# Sheet1.net
KiCad netlist of a schematic drawn in Altium Designer
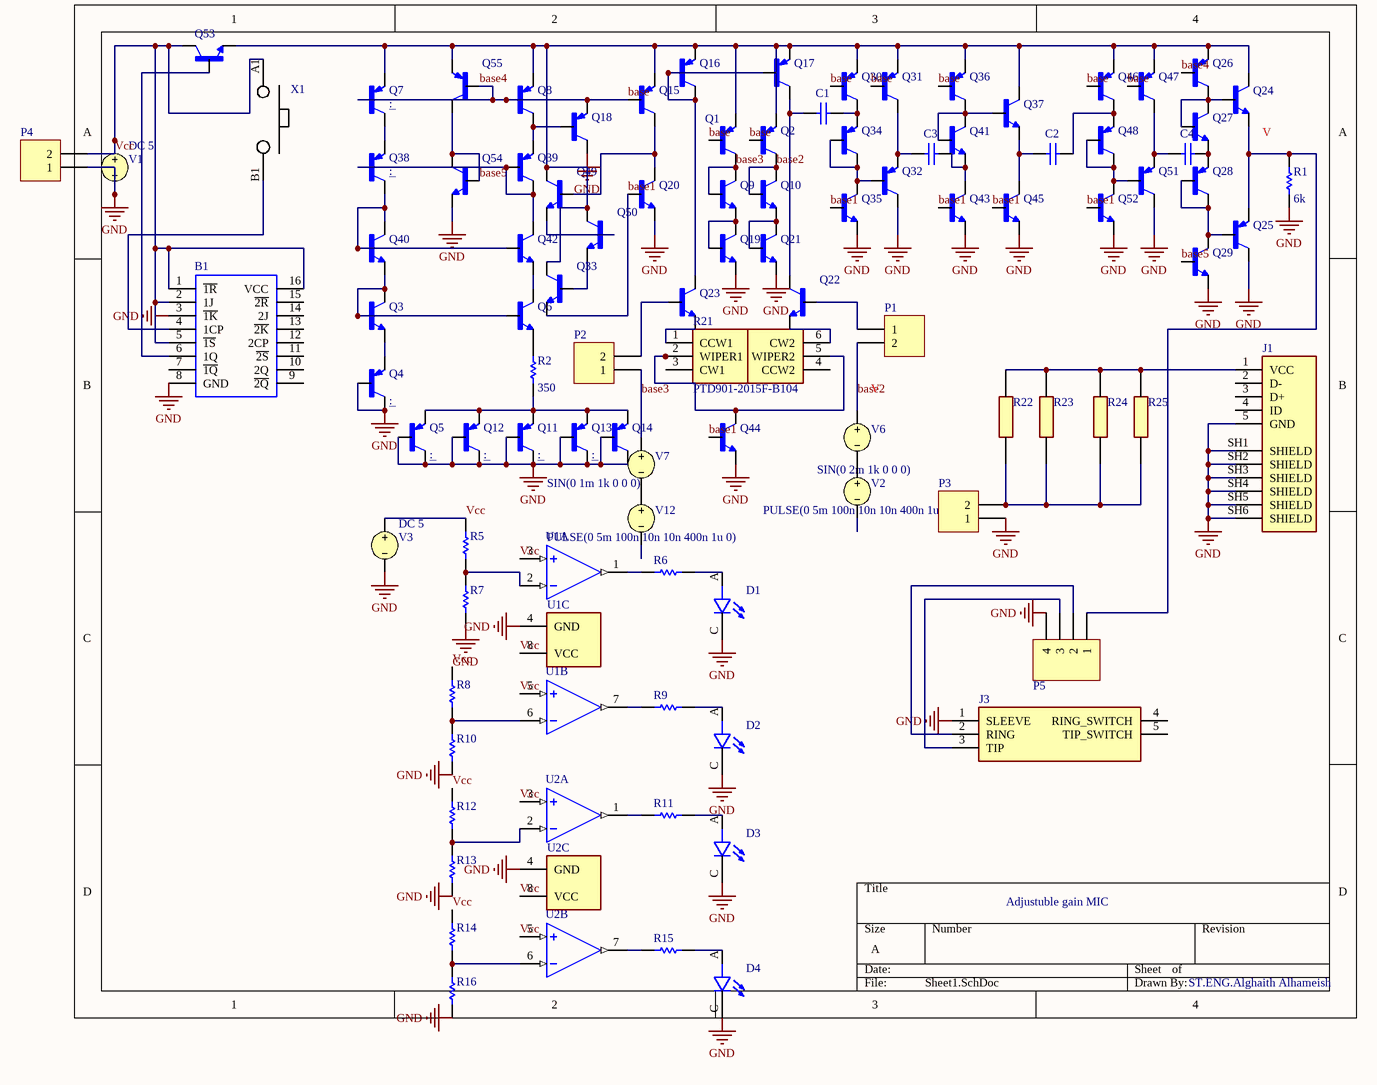
[diagram p0: Sheet1.SchDoc]

(export (version "E")
  (design (tool "Eeschema 10.0.6"))
  (components
    (comp (ref "B1")
      (value "CD74HC109E")
      (footprint "DIP794W53P254L1930H508Q16N")
      (description "High Speed CMOS Logic Dual Positive-Edge-Triggered J-K Flip-Flops with Set and Reset")
      (fields (field (name "MOUSER PART NUMBER") "595-CD74HC109E"))
      (libsource (lib "CD74HC109E") (part "CD74HC109E"))
    )
    (comp (ref "C1")
      (value "Cap")
      (footprint "PCBComponent_1")
      (description "Capacitor")
      (fields (field (name "PUBLISHER") "Altium Limited"))
      (libsource (lib "Miscellaneous Devices") (part "Cap"))
    )
    (comp (ref "C2")
      (value "Cap")
      (footprint "PCBComponent_1")
      (description "Capacitor")
      (fields (field (name "PUBLISHER") "Altium Limited"))
      (libsource (lib "Miscellaneous Devices") (part "Cap"))
    )
    (comp (ref "C3")
      (value "Cap")
      (footprint "PCBComponent_1")
      (description "Capacitor")
      (fields (field (name "PUBLISHER") "Altium Limited"))
      (libsource (lib "Miscellaneous Devices") (part "Cap"))
    )
    (comp (ref "C4")
      (value "Cap")
      (footprint "PCBComponent_1")
      (description "Capacitor")
      (fields (field (name "PUBLISHER") "Altium Limited"))
      (libsource (lib "Miscellaneous Devices") (part "Cap"))
    )
    (comp (ref "D1")
      (value "151054RS03000")
      (footprint "LED_151054RS03000")
      (description "Red 623nm LED Indication - Discrete 1.9V Radial")
      (libsource (lib "151054RS03000") (part "151054RS03000"))
    )
    (comp (ref "D2")
      (value "151054RS03000")
      (footprint "LED_151054RS03000")
      (description "Red 623nm LED Indication - Discrete 1.9V Radial")
      (libsource (lib "151054RS03000") (part "151054RS03000"))
    )
    (comp (ref "D3")
      (value "151054RS03000")
      (footprint "LED_151054RS03000")
      (description "Red 623nm LED Indication - Discrete 1.9V Radial")
      (libsource (lib "151054RS03000") (part "151054RS03000"))
    )
    (comp (ref "D4")
      (value "151054RS03000")
      (footprint "LED_151054RS03000")
      (description "Red 623nm LED Indication - Discrete 1.9V Radial")
      (libsource (lib "151054RS03000") (part "151054RS03000"))
    )
    (comp (ref "J1")
      (value "1932788-1")
      (footprint "TE_1932788-1")
      (description "USB - micro B USB 2.0 Receptacle Connector 5 Position Surface Mount, Right Angle")
      (fields (field (name "MF") "TE Connectivity"))
      (libsource (lib "1932788-1") (part "1932788-1"))
    )
    (comp (ref "J3")
      (value "35RASMT4BHNTRX")
      (footprint "35RASMT4BHNTRX")
      (description "Phone Connectors SMT 3.5MM PHONE JACK")
      (fields (field (name "MOUSER PART NUMBER") "502-35RASMT4BHNTRX"))
      (libsource (lib "35RASMT4BHNTRX") (part "35RASMT4BHNTRX"))
    )
    (comp (ref "P1")
      (value "Header 2")
      (footprint "HDR1X2")
      (description "Header, 2-Pin")
      (fields (field (name "PUBLISHER") "Altium Limited"))
      (libsource (lib "") (part "Header 2_1"))
    )
    (comp (ref "P2")
      (value "Header 2")
      (footprint "HDR1X2")
      (description "Header, 2-Pin")
      (fields (field (name "PUBLISHER") "Altium Limited"))
      (libsource (lib "Miscellaneous Connectors") (part "Header 2"))
    )
    (comp (ref "P3")
      (value "Header 2")
      (footprint "HDR1X2")
      (description "Header, 2-Pin")
      (fields (field (name "PUBLISHER") "Altium Limited"))
      (libsource (lib "Miscellaneous Connectors") (part "Header 2"))
    )
    (comp (ref "P4")
      (value "Header 2")
      (footprint "HDR1X2")
      (description "Header, 2-Pin")
      (fields (field (name "PUBLISHER") "Altium Limited"))
      (libsource (lib "Miscellaneous Connectors") (part "Header 2"))
    )
    (comp (ref "P5")
      (value "Header 4")
      (footprint "HDR1X4")
      (description "Header, 4-Pin")
      (fields (field (name "PUBLISHER") "Altium Limited"))
      (libsource (lib "Miscellaneous Connectors") (part "Header 4"))
    )
    (comp (ref "Q1")
      (value "BC557BRL1G")
      (footprint "TO127P254X732-3")
      (description "Bipolar (BJT) Transistor PNP 45V 100mA 320MHz 625mW Through Hole TO-92-3")
      (fields (field (name "MF") "ON Semiconductor"))
      (libsource (lib "BC557BRL1G") (part "BC557BRL1G"))
    )
    (comp (ref "Q2")
      (value "BC557BRL1G")
      (footprint "TO127P254X732-3")
      (description "Bipolar (BJT) Transistor PNP 45V 100mA 320MHz 625mW Through Hole TO-92-3")
      (fields (field (name "MF") "ON Semiconductor"))
      (libsource (lib "BC557BRL1G") (part "BC557BRL1G"))
    )
    (comp (ref "Q3")
      (value "BC337-40_A1G")
      (footprint "TO127P254X732-3")
      (description "TO-92, 50V, 0.8A, NPN Bipolar Transistor")
      (fields (field (name "MP") "BC337-40 A1G") (field (name "MF") "Taiwan Semiconductor"))
      (libsource (lib "BC337-40_A1G") (part "BC337-40_A1G"))
    )
    (comp (ref "Q4")
      (value "BC557BRL1G")
      (footprint "TO127P254X732-3")
      (description "Bipolar (BJT) Transistor PNP 45V 100mA 320MHz 625mW Through Hole TO-92-3")
      (fields (field (name "MF") "ON Semiconductor"))
      (libsource (lib "BC557BRL1G") (part "BC557BRL1G"))
    )
    (comp (ref "Q5")
      (value "BC557BRL1G")
      (footprint "TO127P254X732-3")
      (description "Bipolar (BJT) Transistor PNP 45V 100mA 320MHz 625mW Through Hole TO-92-3")
      (fields (field (name "MF") "ON Semiconductor"))
      (libsource (lib "BC557BRL1G") (part "BC557BRL1G"))
    )
    (comp (ref "Q6")
      (value "BC337-40_A1G")
      (footprint "TO127P254X732-3")
      (description "TO-92, 50V, 0.8A, NPN Bipolar Transistor")
      (fields (field (name "MP") "BC337-40 A1G") (field (name "MF") "Taiwan Semiconductor"))
      (libsource (lib "BC337-40_A1G") (part "BC337-40_A1G"))
    )
    (comp (ref "Q7")
      (value "BC557BRL1G")
      (footprint "TO127P254X732-3")
      (description "Bipolar (BJT) Transistor PNP 45V 100mA 320MHz 625mW Through Hole TO-92-3 Manufacturer")
      (fields (field (name "MF") "ON Semiconductor"))
      (libsource (lib "BC557BRL1G") (part "BC557BRL1G"))
    )
    (comp (ref "Q8")
      (value "BC557BRL1G")
      (footprint "TO127P254X732-3")
      (description "Bipolar (BJT) Transistor PNP 45V 100mA 320MHz 625mW Through Hole TO-92-3")
      (fields (field (name "MF") "ON Semiconductor"))
      (libsource (lib "BC557BRL1G") (part "BC557BRL1G"))
    )
    (comp (ref "Q9")
      (value "BC337-40_A1G")
      (footprint "TO127P254X732-3")
      (description "TO-92, 50V, 0.8A, NPN Bipolar Transistor")
      (fields (field (name "MP") "BC337-40 A1G") (field (name "MF") "Taiwan Semiconductor"))
      (libsource (lib "BC337-40_A1G") (part "BC337-40_A1G"))
    )
    (comp (ref "Q10")
      (value "BC337-40_A1G")
      (footprint "TO127P254X732-3")
      (description "TO-92, 50V, 0.8A, NPN Bipolar Transistor")
      (fields (field (name "MP") "BC337-40 A1G") (field (name "MF") "Taiwan Semiconductor"))
      (libsource (lib "BC337-40_A1G") (part "BC337-40_A1G"))
    )
    (comp (ref "Q11")
      (value "BC557BRL1G")
      (footprint "TO127P254X732-3")
      (description "Bipolar (BJT) Transistor PNP 45V 100mA 320MHz 625mW Through Hole TO-92-3")
      (fields (field (name "MF") "ON Semiconductor"))
      (libsource (lib "BC557BRL1G") (part "BC557BRL1G"))
    )
    (comp (ref "Q12")
      (value "BC557BRL1G")
      (footprint "TO127P254X732-3")
      (description "Bipolar (BJT) Transistor PNP 45V 100mA 320MHz 625mW Through Hole TO-92-3")
      (fields (field (name "MF") "ON Semiconductor"))
      (libsource (lib "BC557BRL1G") (part "BC557BRL1G"))
    )
    (comp (ref "Q13")
      (value "BC557BRL1G")
      (footprint "TO127P254X732-3")
      (description "Bipolar (BJT) Transistor PNP 45V 100mA 320MHz 625mW Through Hole TO-92-3")
      (fields (field (name "MF") "ON Semiconductor"))
      (libsource (lib "BC557BRL1G") (part "BC557BRL1G"))
    )
    (comp (ref "Q14")
      (value "BC557BRL1G")
      (footprint "TO127P254X732-3")
      (description "Bipolar (BJT) Transistor PNP 45V 100mA 320MHz 625mW Through Hole TO-92-3")
      (fields (field (name "MF") "ON Semiconductor"))
      (libsource (lib "BC557BRL1G") (part "BC557BRL1G"))
    )
    (comp (ref "Q15")
      (value "BC557BRL1G")
      (footprint "TO127P254X732-3")
      (description "Bipolar (BJT) Transistor PNP 45V 100mA 320MHz 625mW Through Hole TO-92-3")
      (fields (field (name "MF") "ON Semiconductor"))
      (libsource (lib "BC557BRL1G") (part "BC557BRL1G"))
    )
    (comp (ref "Q16")
      (value "2n3906")
      (footprint "TO127P254X732-3")
      (description "Bipolar (BJT) Transistor PNP 45V 100mA 320MHz 625mW Through Hole TO-92-3")
      (fields (field (name "MF") "ON Semiconductor") (field (name "MP") "BC557BRL1G"))
      (libsource (lib "BC557BRL1G") (part "BC557BRL1G"))
    )
    (comp (ref "Q17")
      (value "2n3906")
      (footprint "TO127P254X732-3")
      (description "Bipolar (BJT) Transistor PNP 45V 100mA 320MHz 625mW Through Hole TO-92-3")
      (fields (field (name "MF") "ON Semiconductor") (field (name "MP") "BC557BRL1G"))
      (libsource (lib "BC557BRL1G") (part "BC557BRL1G"))
    )
    (comp (ref "Q18")
      (value "BC557BRL1G")
      (footprint "TO127P254X732-3")
      (description "Bipolar (BJT) Transistor PNP 45V 100mA 320MHz 625mW Through Hole TO-92-3")
      (fields (field (name "MF") "ON Semiconductor"))
      (libsource (lib "BC557BRL1G") (part "BC557BRL1G"))
    )
    (comp (ref "Q19")
      (value "BC337-40_A1G")
      (footprint "TO127P254X732-3")
      (description "TO-92, 50V, 0.8A, NPN Bipolar Transistor")
      (fields (field (name "MP") "BC337-40 A1G") (field (name "MF") "Taiwan Semiconductor"))
      (libsource (lib "BC337-40_A1G") (part "BC337-40_A1G"))
    )
    (comp (ref "Q20")
      (value "BC337-40_A1G")
      (footprint "TO127P254X732-3")
      (description "TO-92, 50V, 0.8A, NPN Bipolar Transistor")
      (fields (field (name "MP") "BC337-40 A1G") (field (name "MF") "Taiwan Semiconductor"))
      (libsource (lib "BC337-40_A1G") (part "BC337-40_A1G"))
    )
    (comp (ref "Q21")
      (value "BC337-40_A1G")
      (footprint "TO127P254X732-3")
      (description "TO-92, 50V, 0.8A, NPN Bipolar Transistor")
      (fields (field (name "MP") "BC337-40 A1G") (field (name "MF") "Taiwan Semiconductor"))
      (libsource (lib "BC337-40_A1G") (part "BC337-40_A1G"))
    )
    (comp (ref "Q22")
      (value "2n2222")
      (footprint "TO127P254X732-3")
      (description "TO-92, 50V, 0.8A, NPN Bipolar Transistor")
      (fields (field (name "MP") "BC337-40 A1G") (field (name "MF") "Taiwan Semiconductor"))
      (libsource (lib "") (part "BC337-40_A1G_2"))
    )
    (comp (ref "Q23")
      (value "2n2222")
      (footprint "TO127P254X732-3")
      (description "TO-92, 50V, 0.8A, NPN Bipolar Transistor")
      (fields (field (name "MP") "BC337-40 A1G") (field (name "MF") "Taiwan Semiconductor"))
      (libsource (lib "BC337-40_A1G") (part "BC337-40_A1G"))
    )
    (comp (ref "Q24")
      (value "2n2222")
      (footprint "TO127P254X732-3")
      (description "TO-92, 50V, 0.8A, NPN Bipolar Transistor")
      (fields (field (name "MP") "BC337-40 A1G") (field (name "MF") "Taiwan Semiconductor"))
      (libsource (lib "BC337-40_A1G") (part "BC337-40_A1G"))
    )
    (comp (ref "Q25")
      (value "2n3906")
      (footprint "TO127P254X732-3")
      (description "Bipolar (BJT) Transistor PNP 45V 100mA 320MHz 625mW Through Hole TO-92-3")
      (fields (field (name "MF") "ON Semiconductor") (field (name "MP") "BC557BRL1G"))
      (libsource (lib "BC557BRL1G") (part "BC557BRL1G"))
    )
    (comp (ref "Q26")
      (value "2n3906")
      (footprint "TO127P254X732-3")
      (description "Bipolar (BJT) Transistor PNP 45V 100mA 320MHz 625mW Through Hole TO-92-3")
      (fields (field (name "MF") "ON Semiconductor") (field (name "MP") "BC557BRL1G"))
      (libsource (lib "BC557BRL1G") (part "BC557BRL1G"))
    )
    (comp (ref "Q27")
      (value "2n2222")
      (footprint "TO127P254X732-3")
      (description "TO-92, 50V, 0.8A, NPN Bipolar Transistor")
      (fields (field (name "MP") "BC337-40 A1G") (field (name "MF") "Taiwan Semiconductor"))
      (libsource (lib "BC337-40_A1G") (part "BC337-40_A1G"))
    )
    (comp (ref "Q28")
      (value "2n3906")
      (footprint "TO127P254X732-3")
      (description "Bipolar (BJT) Transistor PNP 45V 100mA 320MHz 625mW Through Hole TO-92-3")
      (fields (field (name "MF") "ON Semiconductor") (field (name "MP") "BC557BRL1G"))
      (libsource (lib "BC557BRL1G") (part "BC557BRL1G"))
    )
    (comp (ref "Q29")
      (value "2n2222")
      (footprint "TO127P254X732-3")
      (description "TO-92, 50V, 0.8A, NPN Bipolar Transistor")
      (fields (field (name "MP") "BC337-40 A1G") (field (name "MF") "Taiwan Semiconductor"))
      (libsource (lib "BC337-40_A1G") (part "BC337-40_A1G"))
    )
    (comp (ref "Q30")
      (value "BC557BRL1G")
      (footprint "TO127P254X732-3")
      (description "Bipolar (BJT) Transistor PNP 45V 100mA 320MHz 625mW Through Hole TO-92-3")
      (fields (field (name "MF") "ON Semiconductor"))
      (libsource (lib "BC557BRL1G") (part "BC557BRL1G"))
    )
    (comp (ref "Q31")
      (value "BC557BRL1G")
      (footprint "TO127P254X732-3")
      (description "Bipolar (BJT) Transistor PNP 45V 100mA 320MHz 625mW Through Hole TO-92-3")
      (fields (field (name "MF") "ON Semiconductor"))
      (libsource (lib "BC557BRL1G") (part "BC557BRL1G"))
    )
    (comp (ref "Q32")
      (value "BC557BRL1G")
      (footprint "TO127P254X732-3")
      (description "Bipolar (BJT) Transistor PNP 45V 100mA 320MHz 625mW Through Hole TO-92-3")
      (fields (field (name "MF") "ON Semiconductor"))
      (libsource (lib "BC557BRL1G") (part "BC557BRL1G"))
    )
    (comp (ref "Q33")
      (value "BC337-40_A1G")
      (footprint "TO127P254X732-3")
      (description "TO-92, 50V, 0.8A, NPN Bipolar Transistor")
      (fields (field (name "MP") "BC337-40 A1G") (field (name "MF") "Taiwan Semiconductor"))
      (libsource (lib "") (part "BC337-40_A1G_2"))
    )
    (comp (ref "Q34")
      (value "BC557BRL1G")
      (footprint "TO127P254X732-3")
      (description "Bipolar (BJT) Transistor PNP 45V 100mA 320MHz 625mW Through Hole TO-92-3")
      (fields (field (name "MF") "ON Semiconductor"))
      (libsource (lib "BC557BRL1G") (part "BC557BRL1G"))
    )
    (comp (ref "Q35")
      (value "BC337-40_A1G")
      (footprint "TO127P254X732-3")
      (description "TO-92, 50V, 0.8A, NPN Bipolar Transistor")
      (fields (field (name "MP") "BC337-40 A1G") (field (name "MF") "Taiwan Semiconductor"))
      (libsource (lib "BC337-40_A1G") (part "BC337-40_A1G"))
    )
    (comp (ref "Q36")
      (value "BC557BRL1G")
      (footprint "TO127P254X732-3")
      (description "Bipolar (BJT) Transistor PNP 45V 100mA 320MHz 625mW Through Hole TO-92-3")
      (fields (field (name "MF") "ON Semiconductor"))
      (libsource (lib "BC557BRL1G") (part "BC557BRL1G"))
    )
    (comp (ref "Q37")
      (value "BC337-40_A1G")
      (footprint "TO127P254X732-3")
      (description "TO-92, 50V, 0.8A, NPN Bipolar Transistor")
      (fields (field (name "MP") "BC337-40 A1G") (field (name "MF") "Taiwan Semiconductor"))
      (libsource (lib "BC337-40_A1G") (part "BC337-40_A1G"))
    )
    (comp (ref "Q38")
      (value "BC557BRL1G")
      (footprint "TO127P254X732-3")
      (description "Bipolar (BJT) Transistor PNP 45V 100mA 320MHz 625mW Through Hole TO-92-3")
      (fields (field (name "MF") "ON Semiconductor"))
      (libsource (lib "BC557BRL1G") (part "BC557BRL1G"))
    )
    (comp (ref "Q39")
      (value "BC557BRL1G")
      (footprint "TO127P254X732-3")
      (description "Bipolar (BJT) Transistor PNP 45V 100mA 320MHz 625mW Through Hole TO-92-3")
      (fields (field (name "MF") "ON Semiconductor"))
      (libsource (lib "BC557BRL1G") (part "BC557BRL1G"))
    )
    (comp (ref "Q40")
      (value "BC337-40_A1G")
      (footprint "TO127P254X732-3")
      (description "TO-92, 50V, 0.8A, NPN Bipolar Transistor")
      (fields (field (name "MP") "BC337-40 A1G") (field (name "MF") "Taiwan Semiconductor"))
      (libsource (lib "BC337-40_A1G") (part "BC337-40_A1G"))
    )
    (comp (ref "Q41")
      (value "BC337-40_A1G")
      (footprint "TO127P254X732-3")
      (description "TO-92, 50V, 0.8A, NPN Bipolar Transistor")
      (fields (field (name "MP") "BC337-40 A1G") (field (name "MF") "Taiwan Semiconductor"))
      (libsource (lib "BC337-40_A1G") (part "BC337-40_A1G"))
    )
    (comp (ref "Q42")
      (value "BC337-40_A1G")
      (footprint "TO127P254X732-3")
      (description "TO-92, 50V, 0.8A, NPN Bipolar Transistor")
      (fields (field (name "MP") "BC337-40 A1G") (field (name "MF") "Taiwan Semiconductor"))
      (libsource (lib "BC337-40_A1G") (part "BC337-40_A1G"))
    )
    (comp (ref "Q43")
      (value "BC337-40_A1G")
      (footprint "TO127P254X732-3")
      (description "TO-92, 50V, 0.8A, NPN Bipolar Transistor")
      (fields (field (name "MP") "BC337-40 A1G") (field (name "MF") "Taiwan Semiconductor"))
      (libsource (lib "BC337-40_A1G") (part "BC337-40_A1G"))
    )
    (comp (ref "Q44")
      (value "BC337-40_A1G")
      (footprint "TO127P254X732-3")
      (description "TO-92, 50V, 0.8A, NPN Bipolar Transistor")
      (fields (field (name "MP") "BC337-40 A1G") (field (name "MF") "Taiwan Semiconductor"))
      (libsource (lib "BC337-40_A1G") (part "BC337-40_A1G"))
    )
    (comp (ref "Q45")
      (value "BC337-40_A1G")
      (footprint "TO127P254X732-3")
      (description "TO-92, 50V, 0.8A, NPN Bipolar Transistor")
      (fields (field (name "MP") "BC337-40 A1G") (field (name "MF") "Taiwan Semiconductor"))
      (libsource (lib "BC337-40_A1G") (part "BC337-40_A1G"))
    )
    (comp (ref "Q46")
      (value "BC557BRL1G")
      (footprint "TO127P254X732-3")
      (description "Bipolar (BJT) Transistor PNP 45V 100mA 320MHz 625mW Through Hole TO-92-3")
      (fields (field (name "MF") "ON Semiconductor"))
      (libsource (lib "BC557BRL1G") (part "BC557BRL1G"))
    )
    (comp (ref "Q47")
      (value "BC557BRL1G")
      (footprint "TO127P254X732-3")
      (description "Bipolar (BJT) Transistor PNP 45V 100mA 320MHz 625mW Through Hole TO-92-3")
      (fields (field (name "MF") "ON Semiconductor"))
      (libsource (lib "BC557BRL1G") (part "BC557BRL1G"))
    )
    (comp (ref "Q48")
      (value "BC557BRL1G")
      (footprint "TO127P254X732-3")
      (description "Bipolar (BJT) Transistor PNP 45V 100mA 320MHz 625mW Through Hole TO-92-3")
      (fields (field (name "MF") "ON Semiconductor"))
      (libsource (lib "BC557BRL1G") (part "BC557BRL1G"))
    )
    (comp (ref "Q49")
      (value "BC337-40_A1G")
      (footprint "TO127P254X732-3")
      (description "TO-92, 50V, 0.8A, NPN Bipolar Transistor")
      (fields (field (name "MP") "BC337-40 A1G") (field (name "MF") "Taiwan Semiconductor"))
      (libsource (lib "") (part "BC337-40_A1G_2"))
    )
    (comp (ref "Q50")
      (value "BC337-40_A1G")
      (footprint "TO127P254X732-3")
      (description "TO-92, 50V, 0.8A, NPN Bipolar Transistor")
      (fields (field (name "MP") "BC337-40 A1G") (field (name "MF") "Taiwan Semiconductor"))
      (libsource (lib "") (part "BC337-40_A1G_2"))
    )
    (comp (ref "Q51")
      (value "BC557BRL1G")
      (footprint "TO127P254X732-3")
      (description "Bipolar (BJT) Transistor PNP 45V 100mA 320MHz 625mW Through Hole TO-92-3")
      (fields (field (name "MF") "ON Semiconductor"))
      (libsource (lib "BC557BRL1G") (part "BC557BRL1G"))
    )
    (comp (ref "Q52")
      (value "BC337-40_A1G")
      (footprint "TO127P254X732-3")
      (description "TO-92, 50V, 0.8A, NPN Bipolar Transistor")
      (fields (field (name "MP") "BC337-40 A1G") (field (name "MF") "Taiwan Semiconductor"))
      (libsource (lib "BC337-40_A1G") (part "BC337-40_A1G"))
    )
    (comp (ref "Q53")
      (value "BC337-40_A1G")
      (footprint "TO127P254X732-3")
      (description "TO-92, 50V, 0.8A, NPN Bipolar Transistor")
      (fields (field (name "MP") "BC337-40 A1G") (field (name "MF") "Taiwan Semiconductor"))
      (libsource (lib "") (part "BC337-40_A1G_1"))
    )
    (comp (ref "Q54")
      (value "BC337-40_A1G")
      (footprint "TO127P254X732-3")
      (description "TO-92, 50V, 0.8A, NPN Bipolar Transistor")
      (fields (field (name "MP") "BC337-40 A1G") (field (name "MF") "Taiwan Semiconductor"))
      (libsource (lib "") (part "BC337-40_A1G_2"))
    )
    (comp (ref "Q55")
      (value "BC557BRL1G")
      (footprint "TO127P254X732-3")
      (description "Bipolar (BJT) Transistor PNP 45V 100mA 320MHz 625mW Through Hole TO-92-3")
      (fields (field (name "MF") "ON Semiconductor"))
      (libsource (lib "") (part "BC557BRL1G_1"))
    )
    (comp (ref "R1")
      (value "6k")
      (footprint "AXIAL-0.3")
      (description "Resistor")
      (fields (field (name "Comment") "Res1") (field (name "PUBLISHER") "Altium Limited"))
      (libsource (lib "Miscellaneous Devices") (part "Res1"))
    )
    (comp (ref "R2")
      (value "350")
      (footprint "AXIAL-0.3")
      (description "Resistor")
      (fields (field (name "Comment") "Res1") (field (name "PUBLISHER") "Altium Limited"))
      (libsource (lib "Miscellaneous Devices") (part "Res1"))
    )
    (comp (ref "R5")
      (value "Res1")
      (footprint "AXIAL-0.3")
      (description "Resistor")
      (fields (field (name "PUBLISHER") "Altium Limited"))
      (libsource (lib "Miscellaneous Devices") (part "Res1"))
    )
    (comp (ref "R6")
      (value "Res1")
      (footprint "AXIAL-0.3")
      (description "Resistor")
      (fields (field (name "PUBLISHER") "Altium Limited"))
      (libsource (lib "Miscellaneous Devices") (part "Res1"))
    )
    (comp (ref "R7")
      (value "Res1")
      (footprint "AXIAL-0.3")
      (description "Resistor")
      (fields (field (name "PUBLISHER") "Altium Limited"))
      (libsource (lib "Miscellaneous Devices") (part "Res1"))
    )
    (comp (ref "R8")
      (value "Res1")
      (footprint "AXIAL-0.3")
      (description "Resistor")
      (fields (field (name "PUBLISHER") "Altium Limited"))
      (libsource (lib "Miscellaneous Devices") (part "Res1"))
    )
    (comp (ref "R9")
      (value "Res1")
      (footprint "AXIAL-0.3")
      (description "Resistor")
      (fields (field (name "PUBLISHER") "Altium Limited"))
      (libsource (lib "Miscellaneous Devices") (part "Res1"))
    )
    (comp (ref "R10")
      (value "Res1")
      (footprint "AXIAL-0.3")
      (description "Resistor")
      (fields (field (name "PUBLISHER") "Altium Limited"))
      (libsource (lib "Miscellaneous Devices") (part "Res1"))
    )
    (comp (ref "R11")
      (value "Res1")
      (footprint "AXIAL-0.3")
      (description "Resistor")
      (fields (field (name "PUBLISHER") "Altium Limited"))
      (libsource (lib "Miscellaneous Devices") (part "Res1"))
    )
    (comp (ref "R12")
      (value "Res1")
      (footprint "AXIAL-0.3")
      (description "Resistor")
      (fields (field (name "PUBLISHER") "Altium Limited"))
      (libsource (lib "Miscellaneous Devices") (part "Res1"))
    )
    (comp (ref "R13")
      (value "Res1")
      (footprint "AXIAL-0.3")
      (description "Resistor")
      (fields (field (name "PUBLISHER") "Altium Limited"))
      (libsource (lib "Miscellaneous Devices") (part "Res1"))
    )
    (comp (ref "R14")
      (value "Res1")
      (footprint "AXIAL-0.3")
      (description "Resistor")
      (fields (field (name "PUBLISHER") "Altium Limited"))
      (libsource (lib "Miscellaneous Devices") (part "Res1"))
    )
    (comp (ref "R15")
      (value "Res1")
      (footprint "AXIAL-0.3")
      (description "Resistor")
      (fields (field (name "PUBLISHER") "Altium Limited"))
      (libsource (lib "Miscellaneous Devices") (part "Res1"))
    )
    (comp (ref "R16")
      (value "Res1")
      (footprint "AXIAL-0.3")
      (description "Resistor")
      (fields (field (name "PUBLISHER") "Altium Limited"))
      (libsource (lib "Miscellaneous Devices") (part "Res1"))
    )
    (comp (ref "R21")
      (value "PTD901-2015F-B104")
      (footprint "PTD9012015FB104")
      (description "Potentiometers PANEL CONTROL 9MM-ST-CARBON")
      (fields (field (name "MOUSER PART NUMBER") "652-PTD9012015FB104"))
      (libsource (lib "PTD901-2015F-B104") (part "PTD901-2015F-B104"))
    )
    (comp (ref "R22")
      (value "MCKNP02SJ0200A10")
      (footprint "RESAD3200W75L1200D500")
      (description "MULTICOMP - MCKNP02SJ0200A10 - RESISTOR, WIREWOUND, 20R, 5%, 2WS")
      (libsource (lib "MCKNP02SJ0200A10") (part "MCKNP02SJ0200A10"))
    )
    (comp (ref "R23")
      (value "MCKNP02SJ0200A10")
      (footprint "RESAD3200W75L1200D500")
      (description "MULTICOMP - MCKNP02SJ0200A10 - RESISTOR, WIREWOUND, 20R, 5%, 2WS")
      (libsource (lib "MCKNP02SJ0200A10") (part "MCKNP02SJ0200A10"))
    )
    (comp (ref "R24")
      (value "MCKNP02SJ0200A10")
      (footprint "RESAD3200W75L1200D500")
      (description "MULTICOMP - MCKNP02SJ0200A10 - RESISTOR, WIREWOUND, 20R, 5%, 2WS")
      (libsource (lib "MCKNP02SJ0200A10") (part "MCKNP02SJ0200A10"))
    )
    (comp (ref "R25")
      (value "MCKNP02SJ0200A10")
      (footprint "RESAD3200W75L1200D500")
      (description "MULTICOMP - MCKNP02SJ0200A10 - RESISTOR, WIREWOUND, 20R, 5%, 2WS")
      (libsource (lib "MCKNP02SJ0200A10") (part "MCKNP02SJ0200A10"))
    )
    (comp (ref "U1")
      (value "LM358PE4")
      (footprint "DIP794W45P254L959H508Q8")
      (description "Dual, 30-V, 700-kHz operational amplifier")
      (fields (field (name "MF") "Texas Instruments"))
      (libsource (lib "LM358PE4") (part "LM358PE4"))
    )
    (comp (ref "U2")
      (value "LM358PE4")
      (footprint "DIP794W45P254L959H508Q8")
      (description "Dual, 30-V, 700-kHz operational amplifier")
      (fields (field (name "MF") "Texas Instruments"))
      (libsource (lib "") (part "LM358PE4_1"))
    )
    (comp (ref "V1")
      (value "DC 5")
      (description "Voltage Source")
      (fields (field (name "PUBLISHER") "Altium Limited"))
      (libsource (lib "Simulation Generic Components") (part "VSRC"))
    )
    (comp (ref "V2")
      (value "PULSE(0 5m 100n 10n 10n 400n 1u 0)")
      (description "Voltage Source")
      (fields (field (name "PUBLISHER") "Altium Limited"))
      (libsource (lib "Simulation Generic Components") (part "VSRC"))
    )
    (comp (ref "V3")
      (value "DC 5")
      (description "Voltage Source")
      (fields (field (name "PUBLISHER") "Altium Limited"))
      (libsource (lib "Simulation Generic Components") (part "VSRC"))
    )
    (comp (ref "V6")
      (value "SIN(0 2m 1k 0 0 0)")
      (description "Voltage Source")
      (fields (field (name "PUBLISHER") "Altium Limited"))
      (libsource (lib "Simulation Generic Components") (part "VSRC"))
    )
    (comp (ref "V7")
      (value "SIN(0 1m 1k 0 0 0)")
      (description "Voltage Source")
      (fields (field (name "PUBLISHER") "Altium Limited"))
      (libsource (lib "Simulation Generic Components") (part "VSRC"))
    )
    (comp (ref "V12")
      (value "PULSE(0 5m 100n 10n 10n 400n 1u 0)")
      (description "Voltage Source")
      (fields (field (name "PUBLISHER") "Altium Limited"))
      (libsource (lib "Simulation Generic Components") (part "VSRC"))
    )
    (comp (ref "X1")
      (value "BUTT-4")
      (footprint "BUTT4")
      (description "Tactile Switches MINI PUSH BUTTON SWITCH 4-PIN QTY. 4")
      (fields (field (name "MOUSER PART NUMBER") "992-BUTT-4"))
      (libsource (lib "BUTT-4") (part "BUTT-4"))
    )
  )
  (nets
    (net (code "1") (name "/Vcc") (class "Default")
      (node (ref "B1") (pin "1") (pinfunction "1R_1") (pintype "passive"))
      (node (ref "B1") (pin "16") (pinfunction "VCC_16") (pintype "power_in"))
      (node (ref "B1") (pin "2") (pinfunction "1J_2") (pintype "passive"))
      (node (ref "B1") (pin "5") (pinfunction "1S_5") (pintype "passive"))
      (node (ref "P4") (pin "2") (pinfunction "2_2") (pintype "passive"))
      (node (ref "Q53") (pin "1") (pinfunction "C_1") (pintype "passive"))
      (node (ref "R12") (pin "2") (pinfunction "2_2") (pintype "passive"))
      (node (ref "R14") (pin "2") (pinfunction "2_2") (pintype "passive"))
      (node (ref "R5") (pin "2") (pinfunction "2_2") (pintype "passive"))
      (node (ref "R8") (pin "2") (pinfunction "2_2") (pintype "passive"))
      (node (ref "U1") (pin "3") (pinfunction "+IN1_3") (pintype "input"))
      (node (ref "U1") (pin "5") (pinfunction "+IN2_5") (pintype "input"))
      (node (ref "U1") (pin "8") (pinfunction "VCC_8") (pintype "power_in"))
      (node (ref "U2") (pin "3") (pinfunction "+IN1_3") (pintype "input"))
      (node (ref "U2") (pin "5") (pinfunction "+IN2_5") (pintype "input"))
      (node (ref "U2") (pin "8") (pinfunction "VCC_8") (pintype "power_in"))
      (node (ref "V1") (pin "1") (pinfunction "1_1") (pintype "passive"))
      (node (ref "V3") (pin "1") (pinfunction "1_1") (pintype "passive"))
      (node (ref "X1") (pin "A1") (pinfunction "A1_A1") (pintype "passive"))
    )
    (net (code "2") (name "/base") (class "Default")
      (node (ref "Q1") (pin "2") (pinfunction "B_2") (pintype "passive"))
      (node (ref "Q15") (pin "2") (pinfunction "B_2") (pintype "passive"))
      (node (ref "Q18") (pin "3") (pinfunction "E_3") (pintype "passive"))
      (node (ref "Q2") (pin "2") (pinfunction "B_2") (pintype "passive"))
      (node (ref "Q26") (pin "2") (pinfunction "B_2") (pintype "passive"))
      (node (ref "Q30") (pin "2") (pinfunction "B_2") (pintype "passive"))
      (node (ref "Q31") (pin "2") (pinfunction "B_2") (pintype "passive"))
      (node (ref "Q36") (pin "2") (pinfunction "B_2") (pintype "passive"))
      (node (ref "Q46") (pin "2") (pinfunction "B_2") (pintype "passive"))
      (node (ref "Q47") (pin "2") (pinfunction "B_2") (pintype "passive"))
      (node (ref "Q55") (pin "2") (pinfunction "B_2") (pintype "passive"))
      (node (ref "Q7") (pin "2") (pinfunction "B_2") (pintype "passive"))
      (node (ref "Q8") (pin "2") (pinfunction "B_2") (pintype "passive"))
    )
    (net (code "3") (name "/base1") (class "Default")
      (node (ref "Q20") (pin "2") (pinfunction "B_2") (pintype "passive"))
      (node (ref "Q33") (pin "3") (pinfunction "E_3") (pintype "passive"))
      (node (ref "Q35") (pin "2") (pinfunction "B_2") (pintype "passive"))
      (node (ref "Q43") (pin "2") (pinfunction "B_2") (pintype "passive"))
      (node (ref "Q44") (pin "2") (pinfunction "B_2") (pintype "passive"))
      (node (ref "Q45") (pin "2") (pinfunction "B_2") (pintype "passive"))
      (node (ref "Q52") (pin "2") (pinfunction "B_2") (pintype "passive"))
    )
    (net (code "4") (name "/base2") (class "Default")
      (node (ref "P1") (pin "2") (pinfunction "2_2") (pintype "passive"))
      (node (ref "Q10") (pin "1") (pinfunction "C_1") (pintype "passive"))
      (node (ref "Q10") (pin "2") (pinfunction "B_2") (pintype "passive"))
      (node (ref "Q2") (pin "1") (pinfunction "C_1") (pintype "passive"))
      (node (ref "V6") (pin "1") (pinfunction "1_1") (pintype "passive"))
    )
    (net (code "5") (name "/base3") (class "Default")
      (node (ref "P2") (pin "1") (pinfunction "1_1") (pintype "passive"))
      (node (ref "Q1") (pin "1") (pinfunction "C_1") (pintype "passive"))
      (node (ref "Q9") (pin "1") (pinfunction "C_1") (pintype "passive"))
      (node (ref "Q9") (pin "2") (pinfunction "B_2") (pintype "passive"))
      (node (ref "V7") (pin "1") (pinfunction "1_1") (pintype "passive"))
    )
    (net (code "6") (name "/base5") (class "Default")
      (node (ref "Q29") (pin "2") (pinfunction "B_2") (pintype "passive"))
      (node (ref "Q54") (pin "1") (pinfunction "C_1") (pintype "passive"))
      (node (ref "Q54") (pin "2") (pinfunction "B_2") (pintype "passive"))
      (node (ref "Q55") (pin "1") (pinfunction "C_1") (pintype "passive"))
    )
    (net (code "7") (name "GND") (class "Default")
      (node (ref "B1") (pin "3") (pinfunction "1K_3") (pintype "passive"))
      (node (ref "B1") (pin "8") (pinfunction "GND_8") (pintype "passive"))
      (node (ref "D1") (pin "C") (pinfunction "C_C") (pintype "passive"))
      (node (ref "D2") (pin "C") (pinfunction "C_C") (pintype "passive"))
      (node (ref "D3") (pin "C") (pinfunction "C_C") (pintype "passive"))
      (node (ref "D4") (pin "C") (pinfunction "C_C") (pintype "passive"))
      (node (ref "J1") (pin "5") (pinfunction "GND_5") (pintype "power_in"))
      (node (ref "J1") (pin "SH1") (pinfunction "SHIELD_SH1") (pintype "passive"))
      (node (ref "J1") (pin "SH2") (pinfunction "SHIELD_SH2") (pintype "passive"))
      (node (ref "J1") (pin "SH3") (pinfunction "SHIELD_SH3") (pintype "passive"))
      (node (ref "J1") (pin "SH4") (pinfunction "SHIELD_SH4") (pintype "passive"))
      (node (ref "J1") (pin "SH5") (pinfunction "SHIELD_SH5") (pintype "passive"))
      (node (ref "J1") (pin "SH6") (pinfunction "SHIELD_SH6") (pintype "passive"))
      (node (ref "J3") (pin "1") (pinfunction "SLEEVE_1") (pintype "passive"))
      (node (ref "P3") (pin "1") (pinfunction "1_1") (pintype "passive"))
      (node (ref "P4") (pin "1") (pinfunction "1_1") (pintype "passive"))
      (node (ref "P5") (pin "4") (pinfunction "4_4") (pintype "passive"))
      (node (ref "Q11") (pin "1") (pinfunction "C_1") (pintype "passive"))
      (node (ref "Q11") (pin "2") (pinfunction "B_2") (pintype "passive"))
      (node (ref "Q12") (pin "1") (pinfunction "C_1") (pintype "passive"))
      (node (ref "Q12") (pin "2") (pinfunction "B_2") (pintype "passive"))
      (node (ref "Q13") (pin "1") (pinfunction "C_1") (pintype "passive"))
      (node (ref "Q13") (pin "2") (pinfunction "B_2") (pintype "passive"))
      (node (ref "Q14") (pin "1") (pinfunction "C_1") (pintype "passive"))
      (node (ref "Q14") (pin "2") (pinfunction "B_2") (pintype "passive"))
      (node (ref "Q18") (pin "1") (pinfunction "C_1") (pintype "passive"))
      (node (ref "Q19") (pin "3") (pinfunction "E_3") (pintype "passive"))
      (node (ref "Q20") (pin "3") (pinfunction "E_3") (pintype "passive"))
      (node (ref "Q21") (pin "3") (pinfunction "E_3") (pintype "passive"))
      (node (ref "Q25") (pin "1") (pinfunction "C_1") (pintype "passive"))
      (node (ref "Q29") (pin "3") (pinfunction "E_3") (pintype "passive"))
      (node (ref "Q32") (pin "1") (pinfunction "C_1") (pintype "passive"))
      (node (ref "Q35") (pin "3") (pinfunction "E_3") (pintype "passive"))
      (node (ref "Q4") (pin "1") (pinfunction "C_1") (pintype "passive"))
      (node (ref "Q4") (pin "2") (pinfunction "B_2") (pintype "passive"))
      (node (ref "Q43") (pin "3") (pinfunction "E_3") (pintype "passive"))
      (node (ref "Q44") (pin "3") (pinfunction "E_3") (pintype "passive"))
      (node (ref "Q45") (pin "3") (pinfunction "E_3") (pintype "passive"))
      (node (ref "Q5") (pin "1") (pinfunction "C_1") (pintype "passive"))
      (node (ref "Q5") (pin "2") (pinfunction "B_2") (pintype "passive"))
      (node (ref "Q51") (pin "1") (pinfunction "C_1") (pintype "passive"))
      (node (ref "Q52") (pin "3") (pinfunction "E_3") (pintype "passive"))
      (node (ref "Q54") (pin "3") (pinfunction "E_3") (pintype "passive"))
      (node (ref "R1") (pin "1") (pinfunction "1_1") (pintype "passive"))
      (node (ref "R10") (pin "1") (pinfunction "1_1") (pintype "passive"))
      (node (ref "R13") (pin "1") (pinfunction "1_1") (pintype "passive"))
      (node (ref "R16") (pin "1") (pinfunction "1_1") (pintype "passive"))
      (node (ref "R7") (pin "1") (pinfunction "1_1") (pintype "passive"))
      (node (ref "U1") (pin "4") (pinfunction "GND_4") (pintype "power_in"))
      (node (ref "U2") (pin "4") (pinfunction "GND_4") (pintype "power_in"))
      (node (ref "V1") (pin "2") (pinfunction "2_2") (pintype "passive"))
      (node (ref "V3") (pin "2") (pinfunction "2_2") (pintype "passive"))
    )
    (net (code "8") (name "Net-(B1-1CP)") (class "Default")
      (node (ref "B1") (pin "4") (pinfunction "1CP_4") (pintype "passive"))
      (node (ref "X1") (pin "B1") (pinfunction "B1_B1") (pintype "passive"))
    )
    (net (code "9") (name "Net-(D1-PadA)") (class "Default")
      (node (ref "D1") (pin "A") (pinfunction "A_A") (pintype "passive"))
      (node (ref "R6") (pin "1") (pinfunction "1_1") (pintype "passive"))
    )
    (net (code "10") (name "Net-(D2-PadA)") (class "Default")
      (node (ref "D2") (pin "A") (pinfunction "A_A") (pintype "passive"))
      (node (ref "R9") (pin "1") (pinfunction "1_1") (pintype "passive"))
    )
    (net (code "11") (name "Net-(D3-PadA)") (class "Default")
      (node (ref "D3") (pin "A") (pinfunction "A_A") (pintype "passive"))
      (node (ref "R11") (pin "1") (pinfunction "1_1") (pintype "passive"))
    )
    (net (code "12") (name "Net-(D4-PadA)") (class "Default")
      (node (ref "D4") (pin "A") (pinfunction "A_A") (pintype "passive"))
      (node (ref "R15") (pin "1") (pinfunction "1_1") (pintype "passive"))
    )
    (net (code "13") (name "Net-(J1-VCC)") (class "Default")
      (node (ref "J1") (pin "1") (pinfunction "VCC_1") (pintype "power_in"))
      (node (ref "R22") (pin "2") (pinfunction "2_2") (pintype "passive"))
      (node (ref "R23") (pin "2") (pinfunction "2_2") (pintype "passive"))
      (node (ref "R24") (pin "2") (pinfunction "2_2") (pintype "passive"))
      (node (ref "R25") (pin "2") (pinfunction "2_2") (pintype "passive"))
    )
    (net (code "14") (name "Net-(J3-RING)") (class "Default")
      (node (ref "J3") (pin "2") (pinfunction "RING_2") (pintype "passive"))
      (node (ref "P5") (pin "2") (pinfunction "2_2") (pintype "passive"))
    )
    (net (code "15") (name "Net-(J3-TIP)") (class "Default")
      (node (ref "J3") (pin "3") (pinfunction "TIP_3") (pintype "passive"))
      (node (ref "P5") (pin "3") (pinfunction "3_3") (pintype "passive"))
    )
    (net (code "16") (name "Net-(P3-Pad2)") (class "Default")
      (node (ref "P3") (pin "2") (pinfunction "2_2") (pintype "passive"))
      (node (ref "R22") (pin "1") (pinfunction "1_1") (pintype "passive"))
      (node (ref "R23") (pin "1") (pinfunction "1_1") (pintype "passive"))
      (node (ref "R24") (pin "1") (pinfunction "1_1") (pintype "passive"))
      (node (ref "R25") (pin "1") (pinfunction "1_1") (pintype "passive"))
    )
    (net (code "17") (name "Net-(Q1-E)") (class "Default")
      (node (ref "Q1") (pin "3") (pinfunction "E_3") (pintype "passive"))
      (node (ref "Q15") (pin "3") (pinfunction "E_3") (pintype "passive"))
      (node (ref "Q16") (pin "3") (pinfunction "E_3") (pintype "passive"))
      (node (ref "Q17") (pin "3") (pinfunction "E_3") (pintype "passive"))
      (node (ref "Q2") (pin "3") (pinfunction "E_3") (pintype "passive"))
      (node (ref "Q24") (pin "1") (pinfunction "C_1") (pintype "passive"))
      (node (ref "Q26") (pin "3") (pinfunction "E_3") (pintype "passive"))
      (node (ref "Q30") (pin "3") (pinfunction "E_3") (pintype "passive"))
      (node (ref "Q31") (pin "3") (pinfunction "E_3") (pintype "passive"))
      (node (ref "Q33") (pin "1") (pinfunction "C_1") (pintype "passive"))
      (node (ref "Q36") (pin "3") (pinfunction "E_3") (pintype "passive"))
      (node (ref "Q37") (pin "1") (pinfunction "C_1") (pintype "passive"))
      (node (ref "Q46") (pin "3") (pinfunction "E_3") (pintype "passive"))
      (node (ref "Q47") (pin "3") (pinfunction "E_3") (pintype "passive"))
      (node (ref "Q49") (pin "1") (pinfunction "C_1") (pintype "passive"))
      (node (ref "Q50") (pin "1") (pinfunction "C_1") (pintype "passive"))
      (node (ref "Q53") (pin "3") (pinfunction "E_3") (pintype "passive"))
      (node (ref "Q55") (pin "3") (pinfunction "E_3") (pintype "passive"))
      (node (ref "Q7") (pin "3") (pinfunction "E_3") (pintype "passive"))
      (node (ref "Q8") (pin "3") (pinfunction "E_3") (pintype "passive"))
    )
    (net (code "18") (name "Net-(Q3-B)") (class "Default")
      (node (ref "Q3") (pin "1") (pinfunction "C_1") (pintype "passive"))
      (node (ref "Q3") (pin "2") (pinfunction "B_2") (pintype "passive"))
      (node (ref "Q40") (pin "3") (pinfunction "E_3") (pintype "passive"))
      (node (ref "Q6") (pin "2") (pinfunction "B_2") (pintype "passive"))
    )
    (net (code "19") (name "Net-(Q3-E)") (class "Default")
      (node (ref "Q3") (pin "3") (pinfunction "E_3") (pintype "passive"))
      (node (ref "Q4") (pin "3") (pinfunction "E_3") (pintype "passive"))
    )
    (net (code "20") (name "Net-(Q6-E)") (class "Default")
      (node (ref "Q6") (pin "3") (pinfunction "E_3") (pintype "passive"))
      (node (ref "R2") (pin "2") (pinfunction "2_2") (pintype "passive"))
    )
    (net (code "21") (name "Net-(Q10-E)") (class "Default")
      (node (ref "Q10") (pin "3") (pinfunction "E_3") (pintype "passive"))
      (node (ref "Q21") (pin "1") (pinfunction "C_1") (pintype "passive"))
      (node (ref "Q21") (pin "2") (pinfunction "B_2") (pintype "passive"))
    )
    (net (code "22") (name "Net-(Q11-E)") (class "Default")
      (node (ref "Q11") (pin "3") (pinfunction "E_3") (pintype "passive"))
      (node (ref "Q12") (pin "3") (pinfunction "E_3") (pintype "passive"))
      (node (ref "Q13") (pin "3") (pinfunction "E_3") (pintype "passive"))
      (node (ref "Q14") (pin "3") (pinfunction "E_3") (pintype "passive"))
      (node (ref "Q5") (pin "3") (pinfunction "E_3") (pintype "passive"))
      (node (ref "R2") (pin "1") (pinfunction "1_1") (pintype "passive"))
    )
    (net (code "23") (name "Net-(Q15-C)") (class "Default")
      (node (ref "Q15") (pin "1") (pinfunction "C_1") (pintype "passive"))
      (node (ref "Q20") (pin "1") (pinfunction "C_1") (pintype "passive"))
      (node (ref "Q49") (pin "2") (pinfunction "B_2") (pintype "passive"))
    )
    (net (code "24") (name "Net-(Q16-B)") (class "Default")
      (node (ref "Q16") (pin "1") (pinfunction "C_1") (pintype "passive"))
      (node (ref "Q16") (pin "2") (pinfunction "B_2") (pintype "passive"))
      (node (ref "Q17") (pin "2") (pinfunction "B_2") (pintype "passive"))
      (node (ref "Q23") (pin "1") (pinfunction "C_1") (pintype "passive"))
    )
    (net (code "25") (name "Net-(Q17-C)") (class "Default")
      (node (ref "C1") (pin "1") (pinfunction "1_1") (pintype "passive"))
      (node (ref "Q17") (pin "1") (pinfunction "C_1") (pintype "passive"))
      (node (ref "Q22") (pin "1") (pinfunction "C_1") (pintype "passive"))
    )
    (net (code "26") (name "Net-(Q18-B)") (class "Default")
      (node (ref "Q18") (pin "2") (pinfunction "B_2") (pintype "passive"))
      (node (ref "Q39") (pin "3") (pinfunction "E_3") (pintype "passive"))
      (node (ref "Q8") (pin "1") (pinfunction "C_1") (pintype "passive"))
    )
    (net (code "27") (name "Net-(Q19-B)") (class "Default")
      (node (ref "Q19") (pin "1") (pinfunction "C_1") (pintype "passive"))
      (node (ref "Q19") (pin "2") (pinfunction "B_2") (pintype "passive"))
      (node (ref "Q9") (pin "3") (pinfunction "E_3") (pintype "passive"))
    )
    (net (code "28") (name "Net-(Q22-B)") (class "Default")
      (node (ref "P1") (pin "1") (pinfunction "1_1") (pintype "passive"))
      (node (ref "Q22") (pin "2") (pinfunction "B_2") (pintype "passive"))
    )
    (net (code "29") (name "Net-(Q22-E)") (class "Default")
      (node (ref "Q22") (pin "3") (pinfunction "E_3") (pintype "passive"))
      (node (ref "R21") (pin "6") (pinfunction "CW2_6") (pintype "passive"))
    )
    (net (code "30") (name "Net-(Q23-B)") (class "Default")
      (node (ref "P2") (pin "2") (pinfunction "2_2") (pintype "passive"))
      (node (ref "Q23") (pin "2") (pinfunction "B_2") (pintype "passive"))
    )
    (net (code "31") (name "Net-(Q23-E)") (class "Default")
      (node (ref "Q23") (pin "3") (pinfunction "E_3") (pintype "passive"))
      (node (ref "R21") (pin "1") (pinfunction "CCW1_1") (pintype "passive"))
    )
    (net (code "32") (name "Net-(Q24-B)") (class "Default")
      (node (ref "Q24") (pin "2") (pinfunction "B_2") (pintype "passive"))
      (node (ref "Q26") (pin "1") (pinfunction "C_1") (pintype "passive"))
      (node (ref "Q27") (pin "1") (pinfunction "C_1") (pintype "passive"))
      (node (ref "Q27") (pin "2") (pinfunction "B_2") (pintype "passive"))
    )
    (net (code "33") (name "Net-(Q24-E)") (class "Default")
      (node (ref "P5") (pin "1") (pinfunction "1_1") (pintype "passive"))
      (node (ref "Q24") (pin "3") (pinfunction "E_3") (pintype "passive"))
      (node (ref "Q25") (pin "3") (pinfunction "E_3") (pintype "passive"))
      (node (ref "R1") (pin "2") (pinfunction "2_2") (pintype "passive"))
    )
    (net (code "34") (name "Net-(Q25-B)") (class "Default")
      (node (ref "Q25") (pin "2") (pinfunction "B_2") (pintype "passive"))
      (node (ref "Q28") (pin "1") (pinfunction "C_1") (pintype "passive"))
      (node (ref "Q28") (pin "2") (pinfunction "B_2") (pintype "passive"))
      (node (ref "Q29") (pin "1") (pinfunction "C_1") (pintype "passive"))
    )
    (net (code "35") (name "Net-(Q27-E)") (class "Default")
      (node (ref "C4") (pin "2") (pinfunction "2_2") (pintype "passive"))
      (node (ref "Q27") (pin "3") (pinfunction "E_3") (pintype "passive"))
      (node (ref "Q28") (pin "3") (pinfunction "E_3") (pintype "passive"))
    )
    (net (code "36") (name "Net-(Q30-C)") (class "Default")
      (node (ref "C1") (pin "2") (pinfunction "2_2") (pintype "passive"))
      (node (ref "Q30") (pin "1") (pinfunction "C_1") (pintype "passive"))
      (node (ref "Q34") (pin "3") (pinfunction "E_3") (pintype "passive"))
    )
    (net (code "37") (name "Net-(Q31-C)") (class "Default")
      (node (ref "C3") (pin "1") (pinfunction "1_1") (pintype "passive"))
      (node (ref "Q31") (pin "1") (pinfunction "C_1") (pintype "passive"))
      (node (ref "Q32") (pin "3") (pinfunction "E_3") (pintype "passive"))
    )
    (net (code "38") (name "Net-(Q32-B)") (class "Default")
      (node (ref "Q32") (pin "2") (pinfunction "B_2") (pintype "passive"))
      (node (ref "Q34") (pin "1") (pinfunction "C_1") (pintype "passive"))
      (node (ref "Q34") (pin "2") (pinfunction "B_2") (pintype "passive"))
      (node (ref "Q35") (pin "1") (pinfunction "C_1") (pintype "passive"))
    )
    (net (code "39") (name "Net-(Q33-B)") (class "Default")
      (node (ref "Q33") (pin "2") (pinfunction "B_2") (pintype "passive"))
      (node (ref "Q50") (pin "3") (pinfunction "E_3") (pintype "passive"))
    )
    (net (code "40") (name "Net-(Q36-C)") (class "Default")
      (node (ref "Q36") (pin "1") (pinfunction "C_1") (pintype "passive"))
      (node (ref "Q37") (pin "2") (pinfunction "B_2") (pintype "passive"))
      (node (ref "Q41") (pin "1") (pinfunction "C_1") (pintype "passive"))
      (node (ref "Q41") (pin "2") (pinfunction "B_2") (pintype "passive"))
    )
    (net (code "41") (name "Net-(Q37-E)") (class "Default")
      (node (ref "C2") (pin "1") (pinfunction "1_1") (pintype "passive"))
      (node (ref "Q37") (pin "3") (pinfunction "E_3") (pintype "passive"))
      (node (ref "Q45") (pin "1") (pinfunction "C_1") (pintype "passive"))
    )
    (net (code "42") (name "Net-(Q38-B)") (class "Default")
      (node (ref "Q38") (pin "2") (pinfunction "B_2") (pintype "passive"))
      (node (ref "Q39") (pin "1") (pinfunction "C_1") (pintype "passive"))
      (node (ref "Q39") (pin "2") (pinfunction "B_2") (pintype "passive"))
      (node (ref "Q42") (pin "1") (pinfunction "C_1") (pintype "passive"))
    )
    (net (code "43") (name "Net-(Q38-C)") (class "Default")
      (node (ref "Q38") (pin "1") (pinfunction "C_1") (pintype "passive"))
      (node (ref "Q40") (pin "1") (pinfunction "C_1") (pintype "passive"))
      (node (ref "Q40") (pin "2") (pinfunction "B_2") (pintype "passive"))
      (node (ref "Q42") (pin "2") (pinfunction "B_2") (pintype "passive"))
    )
    (net (code "44") (name "Net-(Q38-E)") (class "Default")
      (node (ref "Q38") (pin "3") (pinfunction "E_3") (pintype "passive"))
      (node (ref "Q7") (pin "1") (pinfunction "C_1") (pintype "passive"))
    )
    (net (code "45") (name "Net-(Q41-E)") (class "Default")
      (node (ref "C3") (pin "2") (pinfunction "2_2") (pintype "passive"))
      (node (ref "Q41") (pin "3") (pinfunction "E_3") (pintype "passive"))
      (node (ref "Q43") (pin "1") (pinfunction "C_1") (pintype "passive"))
    )
    (net (code "46") (name "Net-(Q42-E)") (class "Default")
      (node (ref "Q42") (pin "3") (pinfunction "E_3") (pintype "passive"))
      (node (ref "Q6") (pin "1") (pinfunction "C_1") (pintype "passive"))
    )
    (net (code "47") (name "Net-(Q44-C)") (class "Default")
      (node (ref "Q44") (pin "1") (pinfunction "C_1") (pintype "passive"))
      (node (ref "R21") (pin "2") (pinfunction "WIPER1_2") (pintype "passive"))
      (node (ref "R21") (pin "5") (pinfunction "WIPER2_5") (pintype "passive"))
    )
    (net (code "48") (name "Net-(Q46-C)") (class "Default")
      (node (ref "C2") (pin "2") (pinfunction "2_2") (pintype "passive"))
      (node (ref "Q46") (pin "1") (pinfunction "C_1") (pintype "passive"))
      (node (ref "Q48") (pin "3") (pinfunction "E_3") (pintype "passive"))
    )
    (net (code "49") (name "Net-(Q47-C)") (class "Default")
      (node (ref "C4") (pin "1") (pinfunction "1_1") (pintype "passive"))
      (node (ref "Q47") (pin "1") (pinfunction "C_1") (pintype "passive"))
      (node (ref "Q51") (pin "3") (pinfunction "E_3") (pintype "passive"))
    )
    (net (code "50") (name "Net-(Q48-B)") (class "Default")
      (node (ref "Q48") (pin "1") (pinfunction "C_1") (pintype "passive"))
      (node (ref "Q48") (pin "2") (pinfunction "B_2") (pintype "passive"))
      (node (ref "Q51") (pin "2") (pinfunction "B_2") (pintype "passive"))
      (node (ref "Q52") (pin "1") (pinfunction "C_1") (pintype "passive"))
    )
    (net (code "51") (name "Net-(Q49-E)") (class "Default")
      (node (ref "Q49") (pin "3") (pinfunction "E_3") (pintype "passive"))
      (node (ref "Q50") (pin "2") (pinfunction "B_2") (pintype "passive"))
    )
    (net (code "52") (name "Net-(Q53-B)") (class "Default")
      (node (ref "B1") (pin "6") (pinfunction "1Q_6") (pintype "passive"))
      (node (ref "Q53") (pin "2") (pinfunction "B_2") (pintype "passive"))
    )
    (net (code "53") (name "Net-(U1A--IN1)") (class "Default")
      (node (ref "R5") (pin "1") (pinfunction "1_1") (pintype "passive"))
      (node (ref "R7") (pin "2") (pinfunction "2_2") (pintype "passive"))
      (node (ref "U1") (pin "2") (pinfunction "-IN1_2") (pintype "input"))
    )
    (net (code "54") (name "Net-(U1A-OUT1)") (class "Default")
      (node (ref "R6") (pin "2") (pinfunction "2_2") (pintype "passive"))
      (node (ref "U1") (pin "1") (pinfunction "OUT1_1") (pintype "output"))
    )
    (net (code "55") (name "Net-(U1B--IN2)") (class "Default")
      (node (ref "R10") (pin "2") (pinfunction "2_2") (pintype "passive"))
      (node (ref "R8") (pin "1") (pinfunction "1_1") (pintype "passive"))
      (node (ref "U1") (pin "6") (pinfunction "-IN2_6") (pintype "input"))
    )
    (net (code "56") (name "Net-(U1B-OUT2)") (class "Default")
      (node (ref "R9") (pin "2") (pinfunction "2_2") (pintype "passive"))
      (node (ref "U1") (pin "7") (pinfunction "OUT2_7") (pintype "output"))
    )
    (net (code "57") (name "Net-(U2A--IN1)") (class "Default")
      (node (ref "R12") (pin "1") (pinfunction "1_1") (pintype "passive"))
      (node (ref "R13") (pin "2") (pinfunction "2_2") (pintype "passive"))
      (node (ref "U2") (pin "2") (pinfunction "-IN1_2") (pintype "input"))
    )
    (net (code "58") (name "Net-(U2A-OUT1)") (class "Default")
      (node (ref "R11") (pin "2") (pinfunction "2_2") (pintype "passive"))
      (node (ref "U2") (pin "1") (pinfunction "OUT1_1") (pintype "output"))
    )
    (net (code "59") (name "Net-(U2B--IN2)") (class "Default")
      (node (ref "R14") (pin "1") (pinfunction "1_1") (pintype "passive"))
      (node (ref "R16") (pin "2") (pinfunction "2_2") (pintype "passive"))
      (node (ref "U2") (pin "6") (pinfunction "-IN2_6") (pintype "input"))
    )
    (net (code "60") (name "Net-(U2B-OUT2)") (class "Default")
      (node (ref "R15") (pin "2") (pinfunction "2_2") (pintype "passive"))
      (node (ref "U2") (pin "7") (pinfunction "OUT2_7") (pintype "output"))
    )
    (net (code "61") (name "Net-(V2-Pad1)") (class "Default")
      (node (ref "V2") (pin "1") (pinfunction "1_1") (pintype "passive"))
      (node (ref "V6") (pin "2") (pinfunction "2_2") (pintype "passive"))
    )
    (net (code "62") (name "Net-(V12-Pad1)") (class "Default")
      (node (ref "V12") (pin "1") (pinfunction "1_1") (pintype "passive"))
      (node (ref "V7") (pin "2") (pinfunction "2_2") (pintype "passive"))
    )
    (net (code "63") (name "unconnected-(B1-1Q-Pad7)") (class "Default")
      (node (ref "B1") (pin "7") (pinfunction "1Q_7") (pintype "passive"))
    )
    (net (code "64") (name "unconnected-(B1-2CP-Pad12)") (class "Default")
      (node (ref "B1") (pin "12") (pinfunction "2CP_12") (pintype "passive"))
    )
    (net (code "65") (name "unconnected-(B1-2J-Pad14)") (class "Default")
      (node (ref "B1") (pin "14") (pinfunction "2J_14") (pintype "passive"))
    )
    (net (code "66") (name "unconnected-(B1-2K-Pad13)") (class "Default")
      (node (ref "B1") (pin "13") (pinfunction "2K_13") (pintype "passive"))
    )
    (net (code "67") (name "unconnected-(B1-2Q-Pad9)") (class "Default")
      (node (ref "B1") (pin "9") (pinfunction "2Q_9") (pintype "passive"))
    )
    (net (code "68") (name "unconnected-(B1-2Q-Pad10)") (class "Default")
      (node (ref "B1") (pin "10") (pinfunction "2Q_10") (pintype "passive"))
    )
    (net (code "69") (name "unconnected-(B1-2R-Pad15)") (class "Default")
      (node (ref "B1") (pin "15") (pinfunction "2R_15") (pintype "passive"))
    )
    (net (code "70") (name "unconnected-(B1-2S-Pad11)") (class "Default")
      (node (ref "B1") (pin "11") (pinfunction "2S_11") (pintype "passive"))
    )
    (net (code "71") (name "unconnected-(J1-D+-Pad3)") (class "Default")
      (node (ref "J1") (pin "3") (pinfunction "D+_3") (pintype "passive"))
    )
    (net (code "72") (name "unconnected-(J1-D--Pad2)") (class "Default")
      (node (ref "J1") (pin "2") (pinfunction "D-_2") (pintype "passive"))
    )
    (net (code "73") (name "unconnected-(J1-ID-Pad4)") (class "Default")
      (node (ref "J1") (pin "4") (pinfunction "ID_4") (pintype "passive"))
    )
    (net (code "74") (name "unconnected-(J3-RING_SWITCH-Pad4)") (class "Default")
      (node (ref "J3") (pin "4") (pinfunction "RING_SWITCH_4") (pintype "passive"))
    )
    (net (code "75") (name "unconnected-(J3-TIP_SWITCH-Pad5)") (class "Default")
      (node (ref "J3") (pin "5") (pinfunction "TIP_SWITCH_5") (pintype "passive"))
    )
    (net (code "76") (name "unconnected-(R21-CCW2-Pad4)") (class "Default")
      (node (ref "R21") (pin "4") (pinfunction "CCW2_4") (pintype "passive"))
    )
    (net (code "77") (name "unconnected-(R21-CW1-Pad3)") (class "Default")
      (node (ref "R21") (pin "3") (pinfunction "CW1_3") (pintype "passive"))
    )
    (net (code "78") (name "unconnected-(V2-Pad2)") (class "Default")
      (node (ref "V2") (pin "2") (pinfunction "2_2") (pintype "passive"))
    )
    (net (code "79") (name "unconnected-(V12-Pad2)") (class "Default")
      (node (ref "V12") (pin "2") (pinfunction "2_2") (pintype "passive"))
    )
  )
)
